# SuperUnioc_v1.net
KiCad netlist of a schematic drawn in EAGLE
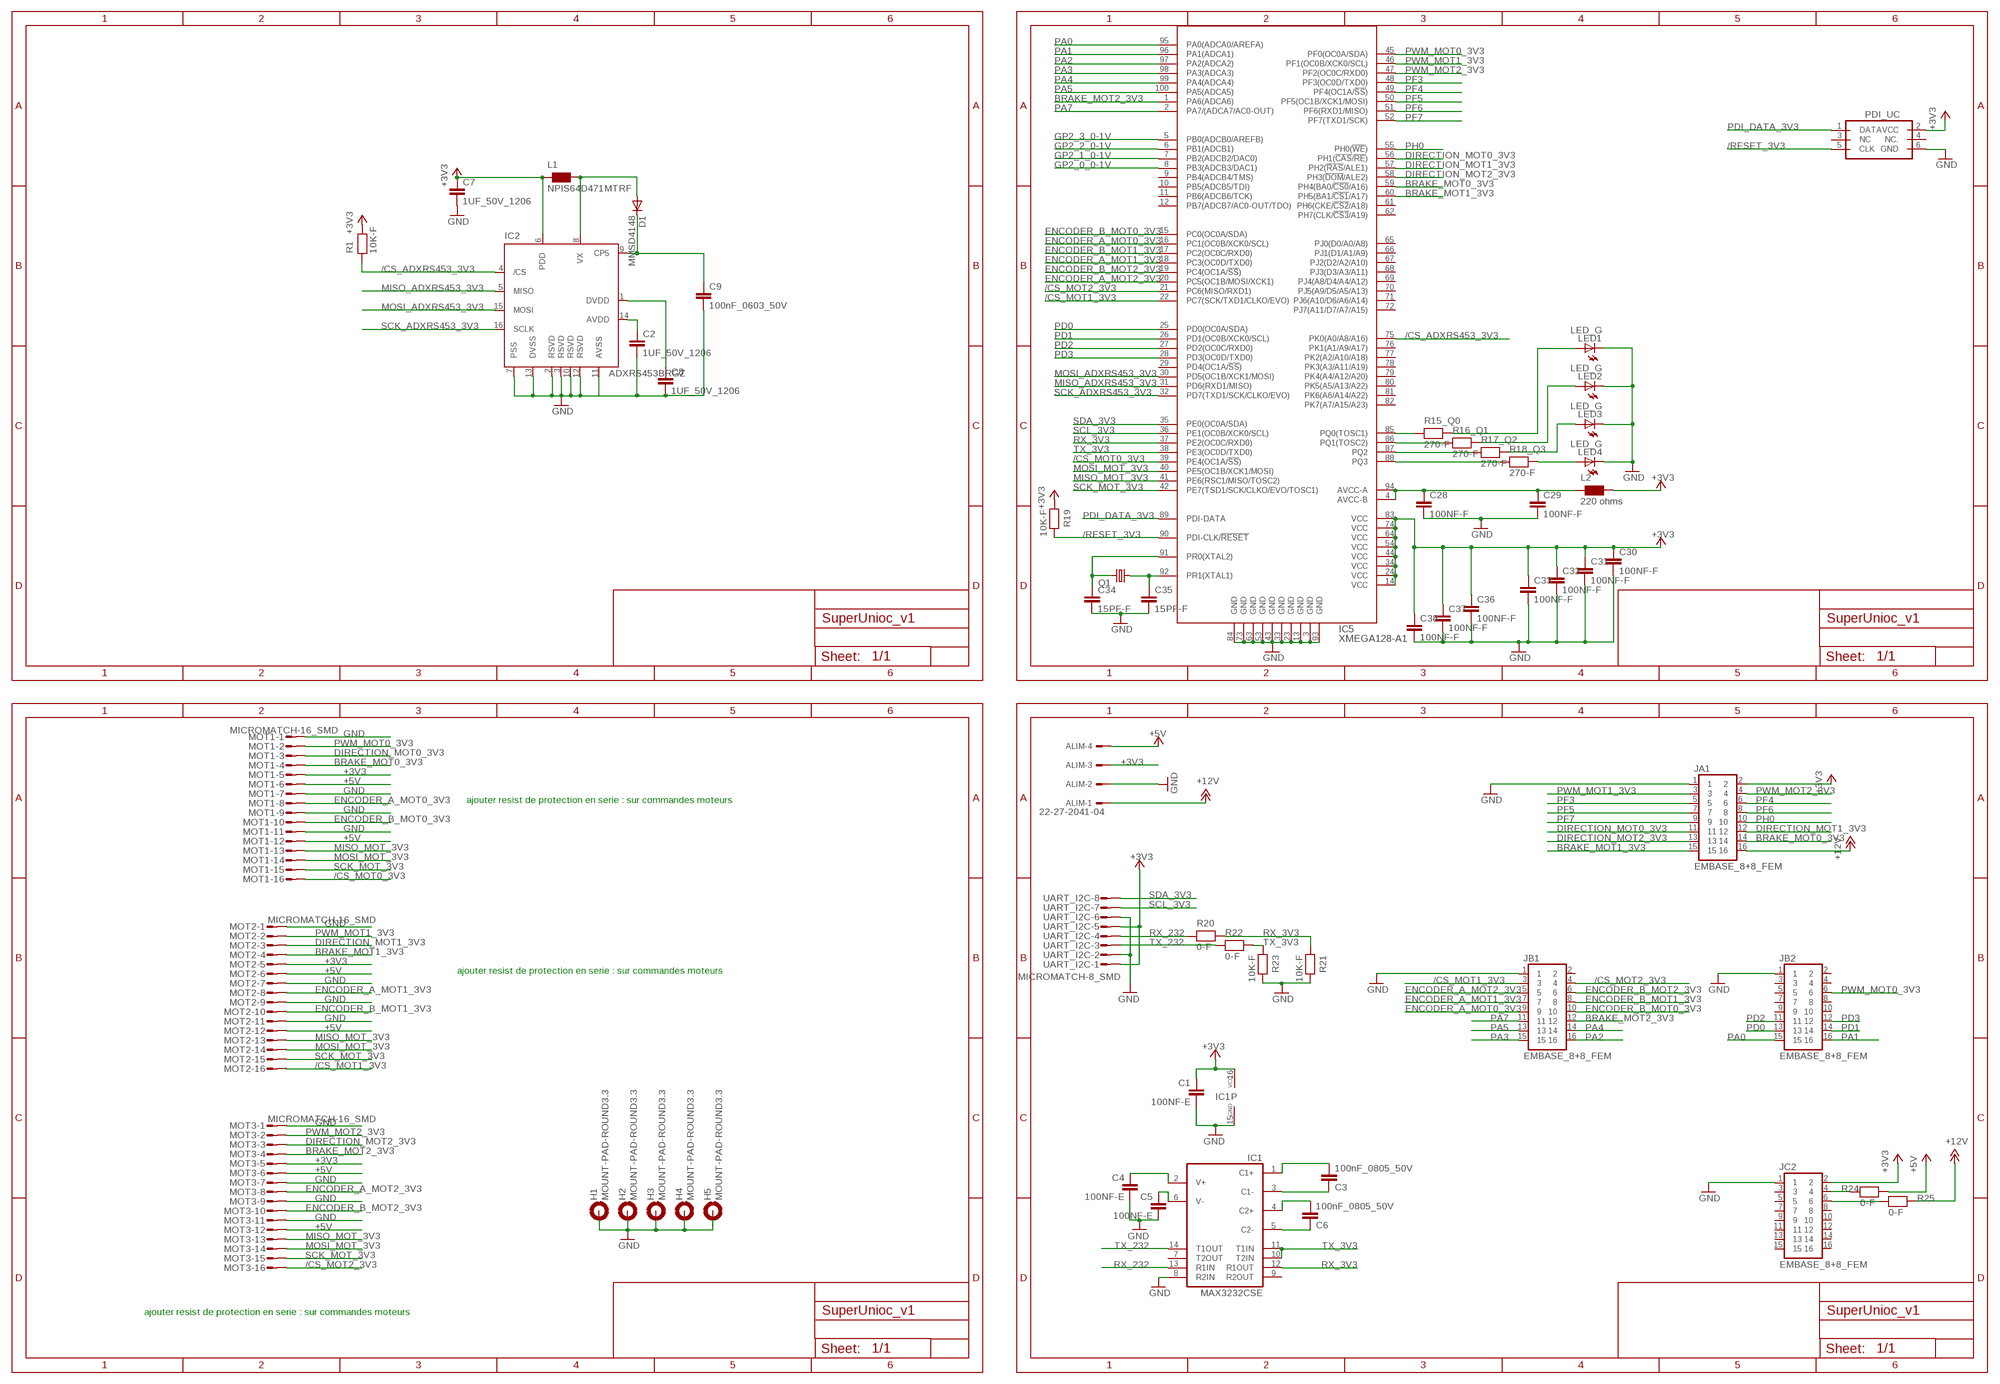
[diagram p0: schematic, sheet 1, part 1 of 2]
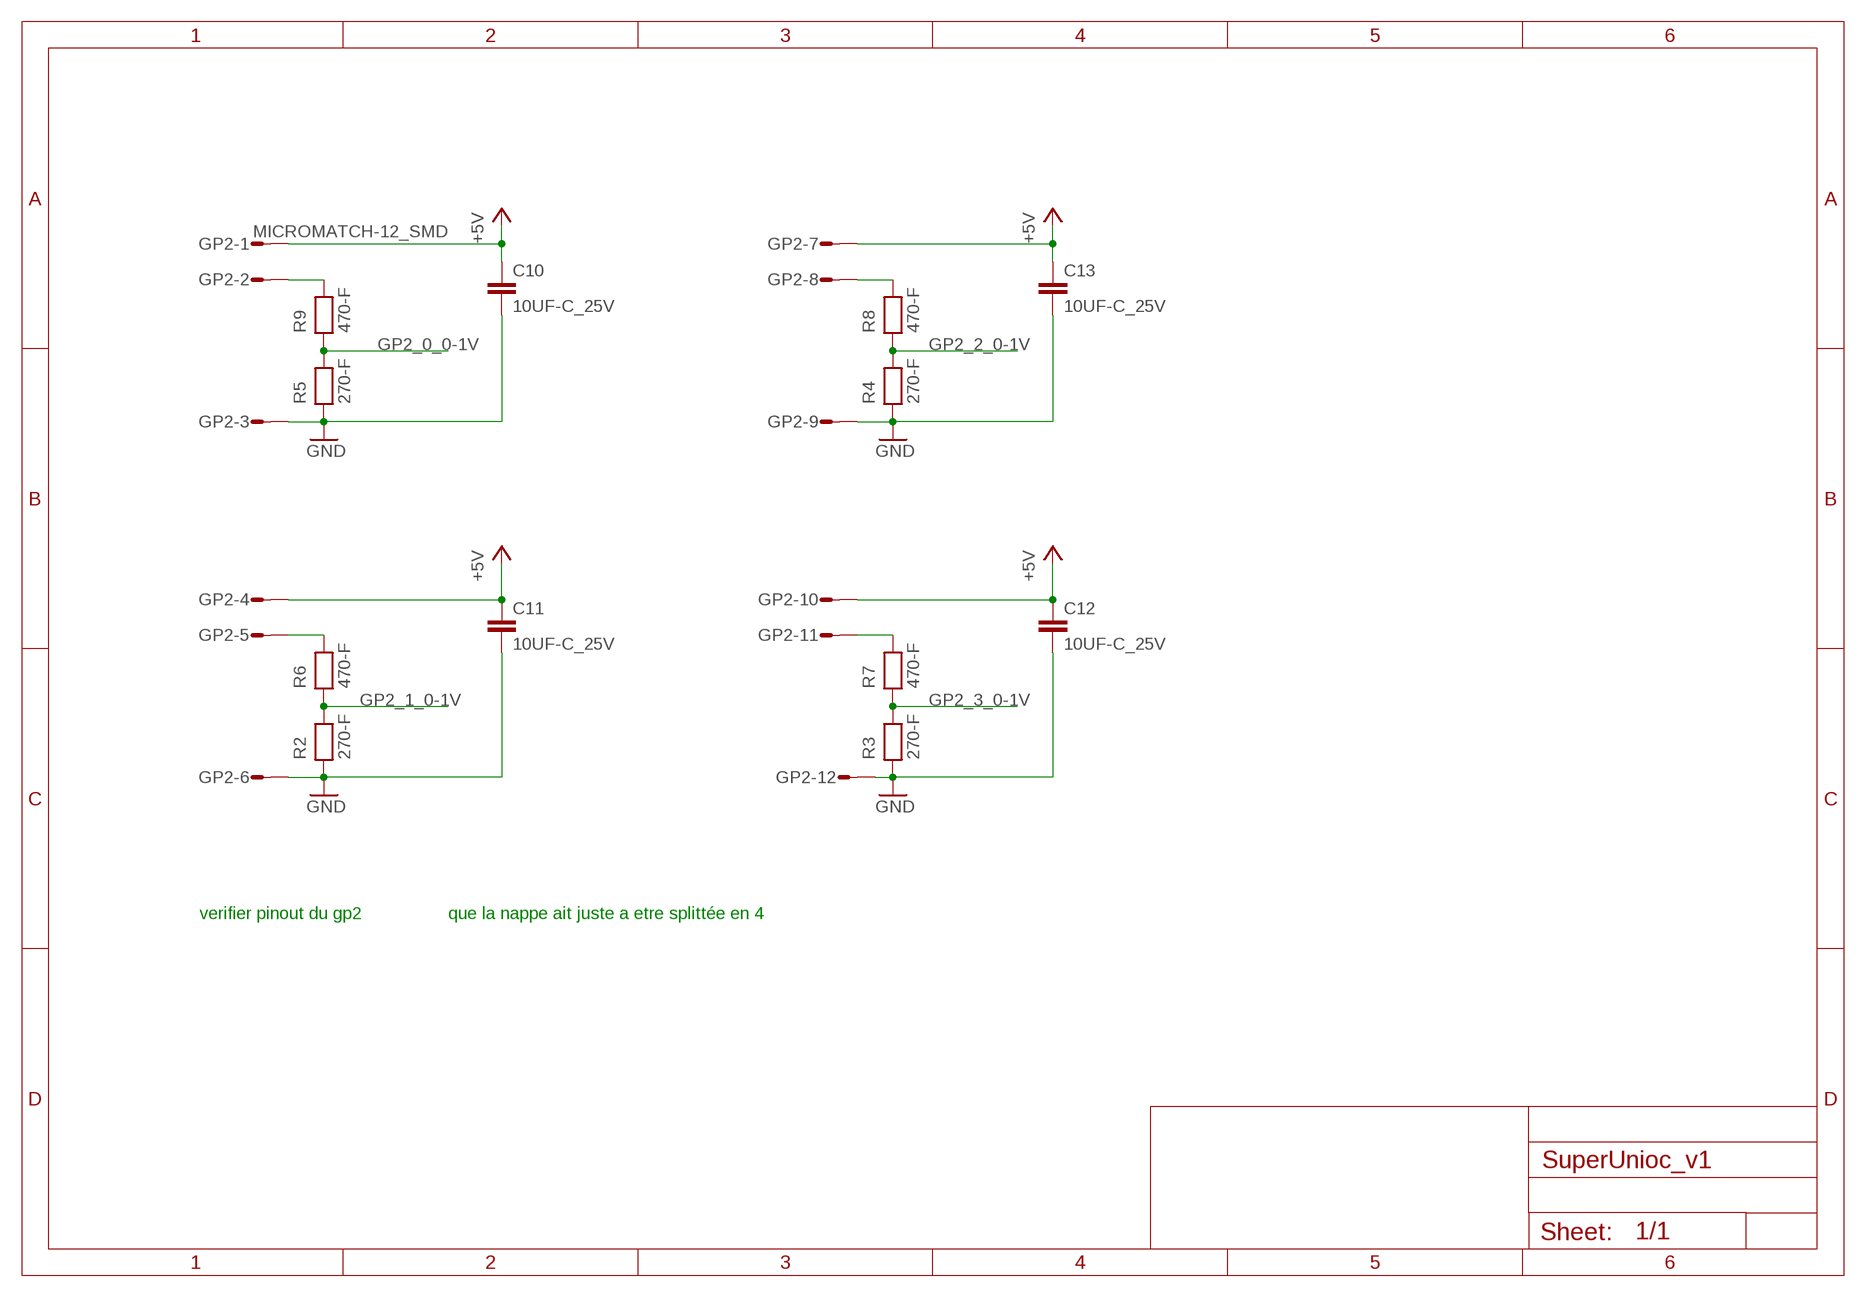
[diagram p1: schematic, sheet 1, part 2 of 2]

(export (version "E")
  (design (tool "Eeschema 10.0.6"))
  (components
    (comp (ref "ALIM")
      (value "22-27-2041-04")
      (footprint "eagle-import:6410-04")
      (libsource (lib "eagle-import") (part "22-?-0427-2041"))
    )
    (comp (ref "C1")
      (value "100NF-E")
      (footprint "eagle-import:C0805")
      (libsource (lib "eagle-import") (part "100NF-E"))
    )
    (comp (ref "C2")
      (value "1UF_50V_1206")
      (footprint "eagle-import:C1206")
      (libsource (lib "eagle-import") (part "1UFD_25V"))
    )
    (comp (ref "C3")
      (value "100nF_0805_50V")
      (footprint "eagle-import:C0805")
      (libsource (lib "eagle-import") (part "100NF-E"))
    )
    (comp (ref "C4")
      (value "100NF-E")
      (footprint "eagle-import:C0805")
      (libsource (lib "eagle-import") (part "100NF-E"))
    )
    (comp (ref "C5")
      (value "100NF-E")
      (footprint "eagle-import:C0805")
      (libsource (lib "eagle-import") (part "100NF-E"))
    )
    (comp (ref "C6")
      (value "100nF_0805_50V")
      (footprint "eagle-import:C0805")
      (libsource (lib "eagle-import") (part "100NF-E"))
    )
    (comp (ref "C7")
      (value "1UF_50V_1206")
      (footprint "eagle-import:C1206")
      (libsource (lib "eagle-import") (part "1UFD_25V"))
    )
    (comp (ref "C8")
      (value "1UF_50V_1206")
      (footprint "eagle-import:C1206")
      (libsource (lib "eagle-import") (part "1UFD_25V"))
    )
    (comp (ref "C9")
      (value "100nF_0603_50V")
      (footprint "eagle-import:C0603")
      (libsource (lib "eagle-import") (part "100NF-F"))
    )
    (comp (ref "C10")
      (value "10UF-C_25V")
      (footprint "eagle-import:C1210")
      (libsource (lib "eagle-import") (part "10UF-C_25V"))
    )
    (comp (ref "C11")
      (value "10UF-C_25V")
      (footprint "eagle-import:C1210")
      (libsource (lib "eagle-import") (part "10UF-C_25V"))
    )
    (comp (ref "C12")
      (value "10UF-C_25V")
      (footprint "eagle-import:C1210")
      (libsource (lib "eagle-import") (part "10UF-C_25V"))
    )
    (comp (ref "C13")
      (value "10UF-C_25V")
      (footprint "eagle-import:C1210")
      (libsource (lib "eagle-import") (part "10UF-C_25V"))
    )
    (comp (ref "C28")
      (value "100NF-F")
      (footprint "eagle-import:C0603")
      (libsource (lib "eagle-import") (part "100NF-F"))
    )
    (comp (ref "C29")
      (value "100NF-F")
      (footprint "eagle-import:C0603")
      (libsource (lib "eagle-import") (part "100NF-F"))
    )
    (comp (ref "C30")
      (value "100NF-F")
      (footprint "eagle-import:C0603")
      (libsource (lib "eagle-import") (part "100NF-F"))
    )
    (comp (ref "C31")
      (value "100NF-F")
      (footprint "eagle-import:C0603")
      (libsource (lib "eagle-import") (part "100NF-F"))
    )
    (comp (ref "C32")
      (value "100NF-F")
      (footprint "eagle-import:C0603")
      (libsource (lib "eagle-import") (part "100NF-F"))
    )
    (comp (ref "C33")
      (value "100NF-F")
      (footprint "eagle-import:C0603")
      (libsource (lib "eagle-import") (part "100NF-F"))
    )
    (comp (ref "C34")
      (value "15PF-F")
      (footprint "eagle-import:C0603")
      (libsource (lib "eagle-import") (part "15PF-F"))
    )
    (comp (ref "C35")
      (value "15PF-F")
      (footprint "eagle-import:C0603")
      (libsource (lib "eagle-import") (part "15PF-F"))
    )
    (comp (ref "C36")
      (value "100NF-F")
      (footprint "eagle-import:C0603")
      (libsource (lib "eagle-import") (part "100NF-F"))
    )
    (comp (ref "C37")
      (value "100NF-F")
      (footprint "eagle-import:C0603")
      (libsource (lib "eagle-import") (part "100NF-F"))
    )
    (comp (ref "C38")
      (value "100NF-F")
      (footprint "eagle-import:C0603")
      (libsource (lib "eagle-import") (part "100NF-F"))
    )
    (comp (ref "D1")
      (value "MMSD4148")
      (footprint "eagle-import:SOD123")
      (libsource (lib "eagle-import") (part "MMSD4148'"))
    )
    (comp (ref "GP2")
      (value "MICROMATCH-12_SMD")
      (footprint "eagle-import:MICROMATCH-12_SMD")
      (libsource (lib "eagle-import") (part "MICROMATCH-12_SMD"))
    )
    (comp (ref "H1")
      (value "MOUNT-PAD-ROUND3.3")
      (footprint "eagle-import:3,3-PAD")
      (libsource (lib "eagle-import") (part "MOUNT-PAD-ROUND3.3"))
    )
    (comp (ref "H2")
      (value "MOUNT-PAD-ROUND3.3")
      (footprint "eagle-import:3,3-PAD")
      (libsource (lib "eagle-import") (part "MOUNT-PAD-ROUND3.3"))
    )
    (comp (ref "H3")
      (value "MOUNT-PAD-ROUND3.3")
      (footprint "eagle-import:3,3-PAD")
      (libsource (lib "eagle-import") (part "MOUNT-PAD-ROUND3.3"))
    )
    (comp (ref "H4")
      (value "MOUNT-PAD-ROUND3.3")
      (footprint "eagle-import:3,3-PAD")
      (libsource (lib "eagle-import") (part "MOUNT-PAD-ROUND3.3"))
    )
    (comp (ref "H5")
      (value "MOUNT-PAD-ROUND3.3")
      (footprint "eagle-import:3,3-PAD")
      (libsource (lib "eagle-import") (part "MOUNT-PAD-ROUND3.3"))
    )
    (comp (ref "IC1")
      (value "MAX3232CSE")
      (footprint "eagle-import:SO16")
      (libsource (lib "eagle-import") (part "MAX3232SEC"))
    )
    (comp (ref "IC2")
      (value "ADXRS453BRGZ")
      (footprint "eagle-import:SO16_CAV")
      (libsource (lib "eagle-import") (part "ADXRS453BRG"))
    )
    (comp (ref "IC5")
      (value "XMEGA128-A1")
      (footprint "eagle-import:TQFP100")
      (libsource (lib "eagle-import") (part "XMEGA-A1TQFP"))
    )
    (comp (ref "JA1")
      (value "EMBASE_8+8_FEM")
      (footprint "eagle-import:EMBASE_8+8_FEM")
      (libsource (lib "eagle-import") (part "EMBASE_8+8_FEM"))
    )
    (comp (ref "JB1")
      (value "EMBASE_8+8_FEM")
      (footprint "eagle-import:EMBASE_8+8_FEM")
      (libsource (lib "eagle-import") (part "EMBASE_8+8_FEM"))
    )
    (comp (ref "JB2")
      (value "EMBASE_8+8_FEM")
      (footprint "eagle-import:EMBASE_8+8_FEM")
      (libsource (lib "eagle-import") (part "EMBASE_8+8_FEM"))
    )
    (comp (ref "JC2")
      (value "EMBASE_8+8_FEM")
      (footprint "eagle-import:EMBASE_8+8_FEM")
      (libsource (lib "eagle-import") (part "EMBASE_8+8_FEM"))
    )
    (comp (ref "L1")
      (value "NPIS64D471MTRF")
      (footprint "eagle-import:NPSIS_D64")
      (libsource (lib "eagle-import") (part "NPIS64D471MTRF"))
    )
    (comp (ref "L2")
      (value "220 ohms")
      (footprint "eagle-import:R0603")
      (libsource (lib "eagle-import") (part "FERRITE_220OHMS"))
    )
    (comp (ref "LED1")
      (value "LED_G")
      (footprint "eagle-import:CHIP-LED0805")
      (libsource (lib "eagle-import") (part "LED_G"))
    )
    (comp (ref "LED2")
      (value "LED_G")
      (footprint "eagle-import:CHIP-LED0805")
      (libsource (lib "eagle-import") (part "LED_G"))
    )
    (comp (ref "LED3")
      (value "LED_G")
      (footprint "eagle-import:CHIP-LED0805")
      (libsource (lib "eagle-import") (part "LED_G"))
    )
    (comp (ref "LED4")
      (value "LED_G")
      (footprint "eagle-import:CHIP-LED0805")
      (libsource (lib "eagle-import") (part "LED_G"))
    )
    (comp (ref "MOT1")
      (value "MICROMATCH-16_SMD")
      (footprint "eagle-import:MICROMATCH-16_SMD")
      (libsource (lib "eagle-import") (part "MICROMATCH-16_SMD"))
    )
    (comp (ref "MOT2")
      (value "MICROMATCH-16_SMD")
      (footprint "eagle-import:MICROMATCH-16_SMD")
      (libsource (lib "eagle-import") (part "MICROMATCH-16_SMD"))
    )
    (comp (ref "MOT3")
      (value "MICROMATCH-16_SMD")
      (footprint "eagle-import:MICROMATCH-16_SMD")
      (libsource (lib "eagle-import") (part "MICROMATCH-16_SMD"))
    )
    (comp (ref "PDI_UC")
      (value "PDI_ATMELL")
      (footprint "eagle-import:ML6L")
      (libsource (lib "eagle-import") (part "PDI_ATMELL"))
    )
    (comp (ref "Q1")
      (value "CRYSTAL_16MHZ_HC49UP")
      (footprint "eagle-import:HC49UP")
      (libsource (lib "eagle-import") (part "CRYSTAL_16MHZ_HC49UP"))
    )
    (comp (ref "R1")
      (value "10K-F")
      (footprint "eagle-import:R0603")
      (libsource (lib "eagle-import") (part "10K-F"))
    )
    (comp (ref "R2")
      (value "270-F")
      (footprint "eagle-import:R0603")
      (libsource (lib "eagle-import") (part "270-F"))
    )
    (comp (ref "R3")
      (value "270-F")
      (footprint "eagle-import:R0603")
      (libsource (lib "eagle-import") (part "270-F"))
    )
    (comp (ref "R4")
      (value "270-F")
      (footprint "eagle-import:R0603")
      (libsource (lib "eagle-import") (part "270-F"))
    )
    (comp (ref "R5")
      (value "270-F")
      (footprint "eagle-import:R0603")
      (libsource (lib "eagle-import") (part "270-F"))
    )
    (comp (ref "R6")
      (value "470-F")
      (footprint "eagle-import:R0603")
      (libsource (lib "eagle-import") (part "470-F"))
    )
    (comp (ref "R7")
      (value "470-F")
      (footprint "eagle-import:R0603")
      (libsource (lib "eagle-import") (part "470-F"))
    )
    (comp (ref "R8")
      (value "470-F")
      (footprint "eagle-import:R0603")
      (libsource (lib "eagle-import") (part "470-F"))
    )
    (comp (ref "R9")
      (value "470-F")
      (footprint "eagle-import:R0603")
      (libsource (lib "eagle-import") (part "470-F"))
    )
    (comp (ref "R15_Q0")
      (value "270-F")
      (footprint "eagle-import:R0603")
      (libsource (lib "eagle-import") (part "270-F"))
    )
    (comp (ref "R16_Q1")
      (value "270-F")
      (footprint "eagle-import:R0603")
      (libsource (lib "eagle-import") (part "270-F"))
    )
    (comp (ref "R17_Q2")
      (value "270-F")
      (footprint "eagle-import:R0603")
      (libsource (lib "eagle-import") (part "270-F"))
    )
    (comp (ref "R18_Q3")
      (value "270-F")
      (footprint "eagle-import:R0603")
      (libsource (lib "eagle-import") (part "270-F"))
    )
    (comp (ref "R19")
      (value "10K-F")
      (footprint "eagle-import:R0603")
      (libsource (lib "eagle-import") (part "10K-F"))
    )
    (comp (ref "R20")
      (value "0-F")
      (footprint "eagle-import:R0603")
      (libsource (lib "eagle-import") (part "0-F"))
    )
    (comp (ref "R21")
      (value "10K-F")
      (footprint "eagle-import:R0603")
      (libsource (lib "eagle-import") (part "10K-F"))
    )
    (comp (ref "R22")
      (value "0-F")
      (footprint "eagle-import:R0603")
      (libsource (lib "eagle-import") (part "0-F"))
    )
    (comp (ref "R23")
      (value "10K-F")
      (footprint "eagle-import:R0603")
      (libsource (lib "eagle-import") (part "10K-F"))
    )
    (comp (ref "R24")
      (value "0-F")
      (footprint "eagle-import:R0603")
      (libsource (lib "eagle-import") (part "0-F"))
    )
    (comp (ref "R25")
      (value "0-F")
      (footprint "eagle-import:R0603")
      (libsource (lib "eagle-import") (part "0-F"))
    )
    (comp (ref "UART_I2C")
      (value "MICROMATCH-8_SMD")
      (footprint "eagle-import:MICROMATCH-8_SMD")
      (libsource (lib "eagle-import") (part "MICROMATCH-8_SMD"))
    )
  )
  (nets
    (net (code "1") (name "+3V3") (class "Default")
      (node (ref "ALIM") (pin "3") (pinfunction "S_3") (pintype "passive"))
      (node (ref "C1") (pin "1") (pinfunction "1_1") (pintype "passive"))
      (node (ref "C30") (pin "1") (pinfunction "1_1") (pintype "passive"))
      (node (ref "C31") (pin "1") (pinfunction "1_1") (pintype "passive"))
      (node (ref "C32") (pin "1") (pinfunction "1_1") (pintype "passive"))
      (node (ref "C33") (pin "1") (pinfunction "1_1") (pintype "passive"))
      (node (ref "C36") (pin "1") (pinfunction "1_1") (pintype "passive"))
      (node (ref "C37") (pin "1") (pinfunction "1_1") (pintype "passive"))
      (node (ref "C38") (pin "1") (pinfunction "1_1") (pintype "passive"))
      (node (ref "C7") (pin "1") (pinfunction "1_1") (pintype "passive"))
      (node (ref "IC1") (pin "16") (pinfunction "VCC_16") (pintype "power_in"))
      (node (ref "IC2") (pin "6") (pinfunction "PDD_6") (pintype "bidirectional"))
      (node (ref "IC5") (pin "14") (pinfunction "VCC_14") (pintype "power_in"))
      (node (ref "IC5") (pin "24") (pinfunction "VCC_24") (pintype "power_in"))
      (node (ref "IC5") (pin "34") (pinfunction "VCC_34") (pintype "power_in"))
      (node (ref "IC5") (pin "44") (pinfunction "VCC_44") (pintype "power_in"))
      (node (ref "IC5") (pin "54") (pinfunction "VCC_54") (pintype "power_in"))
      (node (ref "IC5") (pin "64") (pinfunction "VCC_64") (pintype "power_in"))
      (node (ref "IC5") (pin "74") (pinfunction "VCC_74") (pintype "power_in"))
      (node (ref "IC5") (pin "83") (pinfunction "VCC_83") (pintype "power_in"))
      (node (ref "JA1") (pin "2") (pinfunction "2_2") (pintype "passive"))
      (node (ref "JC2") (pin "2") (pinfunction "2_2") (pintype "passive"))
      (node (ref "L1") (pin "1") (pinfunction "1_1") (pintype "passive"))
      (node (ref "L2") (pin "2") (pinfunction "2_2") (pintype "passive"))
      (node (ref "MOT1") (pin "5") (pinfunction "S_5") (pintype "passive"))
      (node (ref "MOT2") (pin "5") (pinfunction "S_5") (pintype "passive"))
      (node (ref "MOT3") (pin "5") (pinfunction "S_5") (pintype "passive"))
      (node (ref "PDI_UC") (pin "2") (pinfunction "VCC_2") (pintype "passive"))
      (node (ref "R1") (pin "2") (pinfunction "2_2") (pintype "bidirectional"))
      (node (ref "R19") (pin "1") (pinfunction "1_1") (pintype "bidirectional"))
      (node (ref "UART_I2C") (pin "1") (pinfunction "S_1") (pintype "passive"))
      (node (ref "UART_I2C") (pin "5") (pinfunction "S_5") (pintype "passive"))
    )
    (net (code "2") (name "+5V") (class "Default")
      (node (ref "ALIM") (pin "4") (pinfunction "S_4") (pintype "passive"))
      (node (ref "C10") (pin "1") (pinfunction "1_1") (pintype "passive"))
      (node (ref "C11") (pin "1") (pinfunction "1_1") (pintype "passive"))
      (node (ref "C12") (pin "1") (pinfunction "1_1") (pintype "passive"))
      (node (ref "C13") (pin "1") (pinfunction "1_1") (pintype "passive"))
      (node (ref "GP2") (pin "1") (pinfunction "S_1") (pintype "passive"))
      (node (ref "GP2") (pin "10") (pinfunction "S_10") (pintype "passive"))
      (node (ref "GP2") (pin "4") (pinfunction "S_4") (pintype "passive"))
      (node (ref "GP2") (pin "7") (pinfunction "S_7") (pintype "passive"))
      (node (ref "MOT1") (pin "12") (pinfunction "S_12") (pintype "passive"))
      (node (ref "MOT1") (pin "6") (pinfunction "S_6") (pintype "passive"))
      (node (ref "MOT2") (pin "12") (pinfunction "S_12") (pintype "passive"))
      (node (ref "MOT2") (pin "6") (pinfunction "S_6") (pintype "passive"))
      (node (ref "MOT3") (pin "12") (pinfunction "S_12") (pintype "passive"))
      (node (ref "MOT3") (pin "6") (pinfunction "S_6") (pintype "passive"))
      (node (ref "R24") (pin "2") (pinfunction "2_2") (pintype "bidirectional"))
    )
    (net (code "3") (name "+12V") (class "Default")
      (node (ref "ALIM") (pin "1") (pinfunction "S_1") (pintype "passive"))
      (node (ref "JA1") (pin "16") (pinfunction "16_16") (pintype "passive"))
      (node (ref "R25") (pin "2") (pinfunction "2_2") (pintype "bidirectional"))
    )
    (net (code "4") (name "/BRAKE_MOT0_3V3") (class "Default")
      (node (ref "IC5") (pin "59") (pinfunction "PH4(BA0/~{CS0}/A16)_59") (pintype "bidirectional"))
      (node (ref "JA1") (pin "14") (pinfunction "14_14") (pintype "passive"))
      (node (ref "MOT1") (pin "4") (pinfunction "S_4") (pintype "passive"))
    )
    (net (code "5") (name "/BRAKE_MOT1_3V3") (class "Default")
      (node (ref "IC5") (pin "60") (pinfunction "PH5(BA1/~{CS1}/A17)_60") (pintype "bidirectional"))
      (node (ref "JA1") (pin "15") (pinfunction "15_15") (pintype "passive"))
      (node (ref "MOT2") (pin "4") (pinfunction "S_4") (pintype "passive"))
    )
    (net (code "6") (name "/BRAKE_MOT2_3V3") (class "Default")
      (node (ref "IC5") (pin "1") (pinfunction "PA6(ADCA6)_1") (pintype "bidirectional"))
      (node (ref "JB1") (pin "12") (pinfunction "12_12") (pintype "passive"))
      (node (ref "MOT3") (pin "4") (pinfunction "S_4") (pintype "passive"))
    )
    (net (code "7") (name "/DIRECTION_MOT0_3V3") (class "Default")
      (node (ref "IC5") (pin "56") (pinfunction "PH1(~{CAS}/~{RE})_56") (pintype "bidirectional"))
      (node (ref "JA1") (pin "11") (pinfunction "11_11") (pintype "passive"))
      (node (ref "MOT1") (pin "3") (pinfunction "S_3") (pintype "passive"))
    )
    (net (code "8") (name "/DIRECTION_MOT1_3V3") (class "Default")
      (node (ref "IC5") (pin "57") (pinfunction "PH2(~{RAS}/ALE1)_57") (pintype "bidirectional"))
      (node (ref "JA1") (pin "12") (pinfunction "12_12") (pintype "passive"))
      (node (ref "MOT2") (pin "3") (pinfunction "S_3") (pintype "passive"))
    )
    (net (code "9") (name "/DIRECTION_MOT2_3V3") (class "Default")
      (node (ref "IC5") (pin "58") (pinfunction "PH3(~{DOM}/ALE2)_58") (pintype "bidirectional"))
      (node (ref "JA1") (pin "13") (pinfunction "13_13") (pintype "passive"))
      (node (ref "MOT3") (pin "3") (pinfunction "S_3") (pintype "passive"))
    )
    (net (code "10") (name "/ENCODER_A_MOT0_3V3") (class "Default")
      (node (ref "IC5") (pin "16") (pinfunction "PC1(OC0B/XCK0/SCL)_16") (pintype "bidirectional"))
      (node (ref "JB1") (pin "9") (pinfunction "9_9") (pintype "passive"))
      (node (ref "MOT1") (pin "8") (pinfunction "S_8") (pintype "passive"))
    )
    (net (code "11") (name "/ENCODER_A_MOT1_3V3") (class "Default")
      (node (ref "IC5") (pin "18") (pinfunction "PC3(OC0D/TXD0)_18") (pintype "bidirectional"))
      (node (ref "JB1") (pin "7") (pinfunction "7_7") (pintype "passive"))
      (node (ref "MOT2") (pin "8") (pinfunction "S_8") (pintype "passive"))
    )
    (net (code "12") (name "/ENCODER_A_MOT2_3V3") (class "Default")
      (node (ref "IC5") (pin "20") (pinfunction "PC5(OC1B/MOSI/XCK1)_20") (pintype "bidirectional"))
      (node (ref "JB1") (pin "5") (pinfunction "5_5") (pintype "passive"))
      (node (ref "MOT3") (pin "8") (pinfunction "S_8") (pintype "passive"))
    )
    (net (code "13") (name "/ENCODER_B_MOT0_3V3") (class "Default")
      (node (ref "IC5") (pin "15") (pinfunction "PC0(OC0A/SDA)_15") (pintype "bidirectional"))
      (node (ref "JB1") (pin "10") (pinfunction "10_10") (pintype "passive"))
      (node (ref "MOT1") (pin "10") (pinfunction "S_10") (pintype "passive"))
    )
    (net (code "14") (name "/ENCODER_B_MOT1_3V3") (class "Default")
      (node (ref "IC5") (pin "17") (pinfunction "PC2(OC0C/RXD0)_17") (pintype "bidirectional"))
      (node (ref "JB1") (pin "8") (pinfunction "8_8") (pintype "passive"))
      (node (ref "MOT2") (pin "10") (pinfunction "S_10") (pintype "passive"))
    )
    (net (code "15") (name "/ENCODER_B_MOT2_3V3") (class "Default")
      (node (ref "IC5") (pin "19") (pinfunction "PC4(OC1A/~{SS})_19") (pintype "bidirectional"))
      (node (ref "JB1") (pin "6") (pinfunction "6_6") (pintype "passive"))
      (node (ref "MOT3") (pin "10") (pinfunction "S_10") (pintype "passive"))
    )
    (net (code "16") (name "/GP2_0_0-1V") (class "Default")
      (node (ref "IC5") (pin "8") (pinfunction "PB3(ADCB3/DAC1)_8") (pintype "bidirectional"))
      (node (ref "R5") (pin "2") (pinfunction "2_2") (pintype "bidirectional"))
      (node (ref "R9") (pin "1") (pinfunction "1_1") (pintype "bidirectional"))
    )
    (net (code "17") (name "/GP2_1_0-1V") (class "Default")
      (node (ref "IC5") (pin "7") (pinfunction "PB2(ADCB2/DAC0)_7") (pintype "bidirectional"))
      (node (ref "R2") (pin "2") (pinfunction "2_2") (pintype "bidirectional"))
      (node (ref "R6") (pin "1") (pinfunction "1_1") (pintype "bidirectional"))
    )
    (net (code "18") (name "/GP2_2_0-1V") (class "Default")
      (node (ref "IC5") (pin "6") (pinfunction "PB1(ADCB1)_6") (pintype "bidirectional"))
      (node (ref "R4") (pin "2") (pinfunction "2_2") (pintype "bidirectional"))
      (node (ref "R8") (pin "1") (pinfunction "1_1") (pintype "bidirectional"))
    )
    (net (code "19") (name "/GP2_3_0-1V") (class "Default")
      (node (ref "IC5") (pin "5") (pinfunction "PB0(ADCB0/AREFB)_5") (pintype "bidirectional"))
      (node (ref "R3") (pin "2") (pinfunction "2_2") (pintype "bidirectional"))
      (node (ref "R7") (pin "1") (pinfunction "1_1") (pintype "bidirectional"))
    )
    (net (code "20") (name "/MISO_ADXRS453_3V3") (class "Default")
      (node (ref "IC2") (pin "5") (pinfunction "MISO_5") (pintype "bidirectional"))
      (node (ref "IC5") (pin "31") (pinfunction "PD6(RXD1/MISO)_31") (pintype "bidirectional"))
    )
    (net (code "21") (name "/MISO_MOT_3V3") (class "Default")
      (node (ref "IC5") (pin "41") (pinfunction "PE6(RSC1/MISO/TOSC2)_41") (pintype "bidirectional"))
      (node (ref "MOT1") (pin "13") (pinfunction "S_13") (pintype "passive"))
      (node (ref "MOT2") (pin "13") (pinfunction "S_13") (pintype "passive"))
      (node (ref "MOT3") (pin "13") (pinfunction "S_13") (pintype "passive"))
    )
    (net (code "22") (name "/MOSI_ADXRS453_3V3") (class "Default")
      (node (ref "IC2") (pin "15") (pinfunction "MOSI_15") (pintype "bidirectional"))
      (node (ref "IC5") (pin "30") (pinfunction "PD5(OC1B/XCK1/MOSI)_30") (pintype "bidirectional"))
    )
    (net (code "23") (name "/MOSI_MOT_3V3") (class "Default")
      (node (ref "IC5") (pin "40") (pinfunction "PE5(OC1B/XCK1/MOSI)_40") (pintype "bidirectional"))
      (node (ref "MOT1") (pin "14") (pinfunction "S_14") (pintype "passive"))
      (node (ref "MOT2") (pin "14") (pinfunction "S_14") (pintype "passive"))
      (node (ref "MOT3") (pin "14") (pinfunction "S_14") (pintype "passive"))
    )
    (net (code "24") (name "/PA0") (class "Default")
      (node (ref "IC5") (pin "95") (pinfunction "PA0(ADCA0/AREFA)_95") (pintype "bidirectional"))
      (node (ref "JB2") (pin "15") (pinfunction "15_15") (pintype "passive"))
    )
    (net (code "25") (name "/PA1") (class "Default")
      (node (ref "IC5") (pin "96") (pinfunction "PA1(ADCA1)_96") (pintype "bidirectional"))
      (node (ref "JB2") (pin "16") (pinfunction "16_16") (pintype "passive"))
    )
    (net (code "26") (name "/PA2") (class "Default")
      (node (ref "IC5") (pin "97") (pinfunction "PA2(ADCA2)_97") (pintype "bidirectional"))
      (node (ref "JB1") (pin "16") (pinfunction "16_16") (pintype "passive"))
    )
    (net (code "27") (name "/PA3") (class "Default")
      (node (ref "IC5") (pin "98") (pinfunction "PA3(ADCA3)_98") (pintype "bidirectional"))
      (node (ref "JB1") (pin "15") (pinfunction "15_15") (pintype "passive"))
    )
    (net (code "28") (name "/PA4") (class "Default")
      (node (ref "IC5") (pin "99") (pinfunction "PA4(ADCA4)_99") (pintype "bidirectional"))
      (node (ref "JB1") (pin "14") (pinfunction "14_14") (pintype "passive"))
    )
    (net (code "29") (name "/PA5") (class "Default")
      (node (ref "IC5") (pin "100") (pinfunction "PA5(ADCA5)_100") (pintype "bidirectional"))
      (node (ref "JB1") (pin "13") (pinfunction "13_13") (pintype "passive"))
    )
    (net (code "30") (name "/PA7") (class "Default")
      (node (ref "IC5") (pin "2") (pinfunction "PA7/(ADCA7/AC0-OUT)_2") (pintype "bidirectional"))
      (node (ref "JB1") (pin "11") (pinfunction "11_11") (pintype "passive"))
    )
    (net (code "31") (name "/PD0") (class "Default")
      (node (ref "IC5") (pin "25") (pinfunction "PD0(OC0A/SDA)_25") (pintype "bidirectional"))
      (node (ref "JB2") (pin "13") (pinfunction "13_13") (pintype "passive"))
    )
    (net (code "32") (name "/PD1") (class "Default")
      (node (ref "IC5") (pin "26") (pinfunction "PD1(OC0B/XCK0/SCL)_26") (pintype "bidirectional"))
      (node (ref "JB2") (pin "14") (pinfunction "14_14") (pintype "passive"))
    )
    (net (code "33") (name "/PD2") (class "Default")
      (node (ref "IC5") (pin "27") (pinfunction "PD2(OC0C/RXD0)_27") (pintype "bidirectional"))
      (node (ref "JB2") (pin "11") (pinfunction "11_11") (pintype "passive"))
    )
    (net (code "34") (name "/PD3") (class "Default")
      (node (ref "IC5") (pin "28") (pinfunction "PD3(OC0D/TXD0)_28") (pintype "bidirectional"))
      (node (ref "JB2") (pin "12") (pinfunction "12_12") (pintype "passive"))
    )
    (net (code "35") (name "/PDI_DATA_3V3") (class "Default")
      (node (ref "IC5") (pin "89") (pinfunction "PDI-DATA_89") (pintype "bidirectional"))
      (node (ref "PDI_UC") (pin "1") (pinfunction "DATA_1") (pintype "passive"))
    )
    (net (code "36") (name "/PF3") (class "Default")
      (node (ref "IC5") (pin "48") (pinfunction "PF3(OC0D/TXD0)_48") (pintype "bidirectional"))
      (node (ref "JA1") (pin "5") (pinfunction "5_5") (pintype "passive"))
    )
    (net (code "37") (name "/PF4") (class "Default")
      (node (ref "IC5") (pin "49") (pinfunction "PF4(OC1A/~{SS})_49") (pintype "bidirectional"))
      (node (ref "JA1") (pin "6") (pinfunction "6_6") (pintype "passive"))
    )
    (net (code "38") (name "/PF5") (class "Default")
      (node (ref "IC5") (pin "50") (pinfunction "PF5(OC1B/XCK1/MOSI)_50") (pintype "bidirectional"))
      (node (ref "JA1") (pin "7") (pinfunction "7_7") (pintype "passive"))
    )
    (net (code "39") (name "/PF6") (class "Default")
      (node (ref "IC5") (pin "51") (pinfunction "PF6(RXD1/MISO)_51") (pintype "bidirectional"))
      (node (ref "JA1") (pin "8") (pinfunction "8_8") (pintype "passive"))
    )
    (net (code "40") (name "/PF7") (class "Default")
      (node (ref "IC5") (pin "52") (pinfunction "PF7(TXD1/SCK)_52") (pintype "bidirectional"))
      (node (ref "JA1") (pin "9") (pinfunction "9_9") (pintype "passive"))
    )
    (net (code "41") (name "/PH0") (class "Default")
      (node (ref "IC5") (pin "55") (pinfunction "PH0(~{WE})_55") (pintype "bidirectional"))
      (node (ref "JA1") (pin "10") (pinfunction "10_10") (pintype "passive"))
    )
    (net (code "42") (name "/PWM_MOT0_3V3") (class "Default")
      (node (ref "IC5") (pin "45") (pinfunction "PF0(OC0A/SDA)_45") (pintype "bidirectional"))
      (node (ref "JB2") (pin "6") (pinfunction "6_6") (pintype "passive"))
      (node (ref "MOT1") (pin "2") (pinfunction "S_2") (pintype "passive"))
    )
    (net (code "43") (name "/PWM_MOT1_3V3") (class "Default")
      (node (ref "IC5") (pin "46") (pinfunction "PF1(OC0B/XCK0/SCL)_46") (pintype "bidirectional"))
      (node (ref "JA1") (pin "3") (pinfunction "3_3") (pintype "passive"))
      (node (ref "MOT2") (pin "2") (pinfunction "S_2") (pintype "passive"))
    )
    (net (code "44") (name "/PWM_MOT2_3V3") (class "Default")
      (node (ref "IC5") (pin "47") (pinfunction "PF2(OC0C/RXD0)_47") (pintype "bidirectional"))
      (node (ref "JA1") (pin "4") (pinfunction "4_4") (pintype "passive"))
      (node (ref "MOT3") (pin "2") (pinfunction "S_2") (pintype "passive"))
    )
    (net (code "45") (name "/RX_3V3") (class "Default")
      (node (ref "IC1") (pin "12") (pinfunction "R1OUT_12") (pintype "output"))
      (node (ref "IC5") (pin "37") (pinfunction "PE2(OC0C/RXD0)_37") (pintype "bidirectional"))
      (node (ref "R20") (pin "2") (pinfunction "2_2") (pintype "bidirectional"))
      (node (ref "R21") (pin "1") (pinfunction "1_1") (pintype "bidirectional"))
    )
    (net (code "46") (name "/RX_232") (class "Default")
      (node (ref "IC1") (pin "13") (pinfunction "R1IN_13") (pintype "input"))
      (node (ref "R20") (pin "1") (pinfunction "1_1") (pintype "bidirectional"))
      (node (ref "UART_I2C") (pin "4") (pinfunction "S_4") (pintype "passive"))
    )
    (net (code "47") (name "/SCK_ADXRS453_3V3") (class "Default")
      (node (ref "IC2") (pin "16") (pinfunction "SCLK_16") (pintype "bidirectional"))
      (node (ref "IC5") (pin "32") (pinfunction "PD7(TXD1/SCK/CLKO/EVO)_32") (pintype "bidirectional"))
    )
    (net (code "48") (name "/SCK_MOT_3V3") (class "Default")
      (node (ref "IC5") (pin "42") (pinfunction "PE7(TSD1/SCK/CLKO/EVO/TOSC1)_42") (pintype "bidirectional"))
      (node (ref "MOT1") (pin "15") (pinfunction "S_15") (pintype "passive"))
      (node (ref "MOT2") (pin "15") (pinfunction "S_15") (pintype "passive"))
      (node (ref "MOT3") (pin "15") (pinfunction "S_15") (pintype "passive"))
    )
    (net (code "49") (name "/SCL_3V3") (class "Default")
      (node (ref "IC5") (pin "36") (pinfunction "PE1(OC0B/XCK0/SCL)_36") (pintype "bidirectional"))
      (node (ref "UART_I2C") (pin "7") (pinfunction "S_7") (pintype "passive"))
    )
    (net (code "50") (name "/SDA_3V3") (class "Default")
      (node (ref "IC5") (pin "35") (pinfunction "PE0(OC0A/SDA)_35") (pintype "bidirectional"))
      (node (ref "UART_I2C") (pin "8") (pinfunction "S_8") (pintype "passive"))
    )
    (net (code "51") (name "/TX_3V3") (class "Default")
      (node (ref "IC1") (pin "10") (pinfunction "T2IN_10") (pintype "input"))
      (node (ref "IC1") (pin "11") (pinfunction "T1IN_11") (pintype "input"))
      (node (ref "IC5") (pin "38") (pinfunction "PE3(OC0D/TXD0)_38") (pintype "bidirectional"))
      (node (ref "R22") (pin "2") (pinfunction "2_2") (pintype "bidirectional"))
      (node (ref "R23") (pin "1") (pinfunction "1_1") (pintype "bidirectional"))
    )
    (net (code "52") (name "/TX_232") (class "Default")
      (node (ref "IC1") (pin "14") (pinfunction "T1OUT_14") (pintype "output"))
      (node (ref "R22") (pin "1") (pinfunction "1_1") (pintype "bidirectional"))
      (node (ref "UART_I2C") (pin "3") (pinfunction "S_3") (pintype "passive"))
    )
    (net (code "53") (name "/{slash}CS_ADXRS453_3V3") (class "Default")
      (node (ref "IC2") (pin "4") (pinfunction "/CS_4") (pintype "bidirectional"))
      (node (ref "IC5") (pin "75") (pinfunction "PK0(A0/A8/A16)_75") (pintype "bidirectional"))
      (node (ref "R1") (pin "1") (pinfunction "1_1") (pintype "bidirectional"))
    )
    (net (code "54") (name "/{slash}CS_MOT0_3V3") (class "Default")
      (node (ref "IC5") (pin "39") (pinfunction "PE4(OC1A/~{SS})_39") (pintype "bidirectional"))
      (node (ref "MOT1") (pin "16") (pinfunction "S_16") (pintype "passive"))
    )
    (net (code "55") (name "/{slash}CS_MOT1_3V3") (class "Default")
      (node (ref "IC5") (pin "22") (pinfunction "PC7(SCK/TXD1/CLKO/EVO)_22") (pintype "bidirectional"))
      (node (ref "JB1") (pin "3") (pinfunction "3_3") (pintype "passive"))
      (node (ref "MOT2") (pin "16") (pinfunction "S_16") (pintype "passive"))
    )
    (net (code "56") (name "/{slash}CS_MOT2_3V3") (class "Default")
      (node (ref "IC5") (pin "21") (pinfunction "PC6(MISO/RXD1)_21") (pintype "bidirectional"))
      (node (ref "JB1") (pin "4") (pinfunction "4_4") (pintype "passive"))
      (node (ref "MOT3") (pin "16") (pinfunction "S_16") (pintype "passive"))
    )
    (net (code "57") (name "/{slash}RESET_3V3") (class "Default")
      (node (ref "IC5") (pin "90") (pinfunction "PDI-CLK/~{RESET}_90") (pintype "input"))
      (node (ref "PDI_UC") (pin "5") (pinfunction "CLK_5") (pintype "passive"))
      (node (ref "R19") (pin "2") (pinfunction "2_2") (pintype "bidirectional"))
    )
    (net (code "58") (name "GND") (class "Default")
      (node (ref "ALIM") (pin "2") (pinfunction "S_2") (pintype "passive"))
      (node (ref "C1") (pin "2") (pinfunction "2_2") (pintype "passive"))
      (node (ref "C10") (pin "2") (pinfunction "2_2") (pintype "passive"))
      (node (ref "C11") (pin "2") (pinfunction "2_2") (pintype "passive"))
      (node (ref "C12") (pin "2") (pinfunction "2_2") (pintype "passive"))
      (node (ref "C13") (pin "2") (pinfunction "2_2") (pintype "passive"))
      (node (ref "C2") (pin "2") (pinfunction "2_2") (pintype "passive"))
      (node (ref "C28") (pin "2") (pinfunction "2_2") (pintype "passive"))
      (node (ref "C29") (pin "2") (pinfunction "2_2") (pintype "passive"))
      (node (ref "C30") (pin "2") (pinfunction "2_2") (pintype "passive"))
      (node (ref "C31") (pin "2") (pinfunction "2_2") (pintype "passive"))
      (node (ref "C32") (pin "2") (pinfunction "2_2") (pintype "passive"))
      (node (ref "C33") (pin "2") (pinfunction "2_2") (pintype "passive"))
      (node (ref "C34") (pin "2") (pinfunction "2_2") (pintype "passive"))
      (node (ref "C35") (pin "2") (pinfunction "2_2") (pintype "passive"))
      (node (ref "C36") (pin "2") (pinfunction "2_2") (pintype "passive"))
      (node (ref "C37") (pin "2") (pinfunction "2_2") (pintype "passive"))
      (node (ref "C38") (pin "2") (pinfunction "2_2") (pintype "passive"))
      (node (ref "C4") (pin "2") (pinfunction "2_2") (pintype "passive"))
      (node (ref "C5") (pin "2") (pinfunction "2_2") (pintype "passive"))
      (node (ref "C7") (pin "2") (pinfunction "2_2") (pintype "passive"))
      (node (ref "C8") (pin "2") (pinfunction "2_2") (pintype "passive"))
      (node (ref "C9") (pin "2") (pinfunction "2_2") (pintype "passive"))
      (node (ref "GP2") (pin "12") (pinfunction "S_12") (pintype "passive"))
      (node (ref "GP2") (pin "3") (pinfunction "S_3") (pintype "passive"))
      (node (ref "GP2") (pin "6") (pinfunction "S_6") (pintype "passive"))
      (node (ref "GP2") (pin "9") (pinfunction "S_9") (pintype "passive"))
      (node (ref "H1") (pin "B3,3") (pinfunction "MOUNT_B3,3") (pintype "passive"))
      (node (ref "H2") (pin "B3,3") (pinfunction "MOUNT_B3,3") (pintype "passive"))
      (node (ref "H3") (pin "B3,3") (pinfunction "MOUNT_B3,3") (pintype "passive"))
      (node (ref "H4") (pin "B3,3") (pinfunction "MOUNT_B3,3") (pintype "passive"))
      (node (ref "H5") (pin "B3,3") (pinfunction "MOUNT_B3,3") (pintype "passive"))
      (node (ref "IC1") (pin "15") (pinfunction "GND_15") (pintype "power_in"))
      (node (ref "IC1") (pin "8") (pinfunction "R2IN_8") (pintype "input"))
      (node (ref "IC2") (pin "10") (pinfunction "RSVD_10") (pintype "bidirectional"))
      (node (ref "IC2") (pin "11") (pinfunction "AVSS_11") (pintype "bidirectional"))
      (node (ref "IC2") (pin "12") (pinfunction "RSVD_12") (pintype "bidirectional"))
      (node (ref "IC2") (pin "13") (pinfunction "DVSS_13") (pintype "bidirectional"))
      (node (ref "IC2") (pin "2") (pinfunction "RSVD_2") (pintype "bidirectional"))
      (node (ref "IC2") (pin "3") (pinfunction "RSVD_3") (pintype "bidirectional"))
      (node (ref "IC2") (pin "7") (pinfunction "PSS_7") (pintype "bidirectional"))
      (node (ref "IC5") (pin "13") (pinfunction "GND_13") (pintype "power_in"))
      (node (ref "IC5") (pin "23") (pinfunction "GND_23") (pintype "power_in"))
      (node (ref "IC5") (pin "3") (pinfunction "GND_3") (pintype "power_in"))
      (node (ref "IC5") (pin "33") (pinfunction "GND_33") (pintype "power_in"))
      (node (ref "IC5") (pin "43") (pinfunction "GND_43") (pintype "power_in"))
      (node (ref "IC5") (pin "53") (pinfunction "GND_53") (pintype "power_in"))
      (node (ref "IC5") (pin "63") (pinfunction "GND_63") (pintype "power_in"))
      (node (ref "IC5") (pin "73") (pinfunction "GND_73") (pintype "power_in"))
      (node (ref "IC5") (pin "84") (pinfunction "GND_84") (pintype "power_in"))
      (node (ref "IC5") (pin "93") (pinfunction "GND_93") (pintype "power_in"))
      (node (ref "JA1") (pin "1") (pinfunction "1_1") (pintype "passive"))
      (node (ref "JB1") (pin "1") (pinfunction "1_1") (pintype "passive"))
      (node (ref "JB2") (pin "1") (pinfunction "1_1") (pintype "passive"))
      (node (ref "JC2") (pin "1") (pinfunction "1_1") (pintype "passive"))
      (node (ref "LED1") (pin "C") (pinfunction "C_C") (pintype "passive"))
      (node (ref "LED2") (pin "C") (pinfunction "C_C") (pintype "passive"))
      (node (ref "LED3") (pin "C") (pinfunction "C_C") (pintype "passive"))
      (node (ref "LED4") (pin "C") (pinfunction "C_C") (pintype "passive"))
      (node (ref "MOT1") (pin "1") (pinfunction "S_1") (pintype "passive"))
      (node (ref "MOT1") (pin "11") (pinfunction "S_11") (pintype "passive"))
      (node (ref "MOT1") (pin "7") (pinfunction "S_7") (pintype "passive"))
      (node (ref "MOT1") (pin "9") (pinfunction "S_9") (pintype "passive"))
      (node (ref "MOT2") (pin "1") (pinfunction "S_1") (pintype "passive"))
      (node (ref "MOT2") (pin "11") (pinfunction "S_11") (pintype "passive"))
      (node (ref "MOT2") (pin "7") (pinfunction "S_7") (pintype "passive"))
      (node (ref "MOT2") (pin "9") (pinfunction "S_9") (pintype "passive"))
      (node (ref "MOT3") (pin "1") (pinfunction "S_1") (pintype "passive"))
      (node (ref "MOT3") (pin "11") (pinfunction "S_11") (pintype "passive"))
      (node (ref "MOT3") (pin "7") (pinfunction "S_7") (pintype "passive"))
      (node (ref "MOT3") (pin "9") (pinfunction "S_9") (pintype "passive"))
      (node (ref "PDI_UC") (pin "6") (pinfunction "GND_6") (pintype "passive"))
      (node (ref "R2") (pin "1") (pinfunction "1_1") (pintype "bidirectional"))
      (node (ref "R21") (pin "2") (pinfunction "2_2") (pintype "bidirectional"))
      (node (ref "R23") (pin "2") (pinfunction "2_2") (pintype "bidirectional"))
      (node (ref "R3") (pin "1") (pinfunction "1_1") (pintype "bidirectional"))
      (node (ref "R4") (pin "1") (pinfunction "1_1") (pintype "bidirectional"))
      (node (ref "R5") (pin "1") (pinfunction "1_1") (pintype "bidirectional"))
      (node (ref "UART_I2C") (pin "2") (pinfunction "S_2") (pintype "passive"))
      (node (ref "UART_I2C") (pin "6") (pinfunction "S_6") (pintype "passive"))
    )
    (net (code "59") (name "Net-(GP2C-S)") (class "Default")
      (node (ref "GP2") (pin "11") (pinfunction "S_11") (pintype "passive"))
      (node (ref "R7") (pin "2") (pinfunction "2_2") (pintype "bidirectional"))
    )
    (net (code "60") (name "Net-(GP2E-S)") (class "Default")
      (node (ref "GP2") (pin "2") (pinfunction "S_2") (pintype "passive"))
      (node (ref "R9") (pin "2") (pinfunction "2_2") (pintype "bidirectional"))
    )
    (net (code "61") (name "Net-(GP2H-S)") (class "Default")
      (node (ref "GP2") (pin "5") (pinfunction "S_5") (pintype "passive"))
      (node (ref "R6") (pin "2") (pinfunction "2_2") (pintype "bidirectional"))
    )
    (net (code "62") (name "Net-(GP2K-S)") (class "Default")
      (node (ref "GP2") (pin "8") (pinfunction "S_8") (pintype "passive"))
      (node (ref "R8") (pin "2") (pinfunction "2_2") (pintype "bidirectional"))
    )
    (net (code "63") (name "Net-(IC1A-C1+)") (class "Default")
      (node (ref "C3") (pin "1") (pinfunction "1_1") (pintype "passive"))
      (node (ref "IC1") (pin "1") (pinfunction "C1+_1") (pintype "bidirectional"))
    )
    (net (code "64") (name "Net-(IC1A-C1-)") (class "Default")
      (node (ref "C3") (pin "2") (pinfunction "2_2") (pintype "passive"))
      (node (ref "IC1") (pin "3") (pinfunction "C1-_3") (pintype "bidirectional"))
    )
    (net (code "65") (name "Net-(IC1A-C2+)") (class "Default")
      (node (ref "C6") (pin "1") (pinfunction "1_1") (pintype "passive"))
      (node (ref "IC1") (pin "4") (pinfunction "C2+_4") (pintype "bidirectional"))
    )
    (net (code "66") (name "Net-(IC1A-C2-)") (class "Default")
      (node (ref "C6") (pin "2") (pinfunction "2_2") (pintype "passive"))
      (node (ref "IC1") (pin "5") (pinfunction "C2-_5") (pintype "bidirectional"))
    )
    (net (code "67") (name "Net-(IC1A-V+)") (class "Default")
      (node (ref "C4") (pin "1") (pinfunction "1_1") (pintype "passive"))
      (node (ref "IC1") (pin "2") (pinfunction "V+_2") (pintype "bidirectional"))
    )
    (net (code "68") (name "Net-(IC1A-V-)") (class "Default")
      (node (ref "C5") (pin "1") (pinfunction "1_1") (pintype "passive"))
      (node (ref "IC1") (pin "6") (pinfunction "V-_6") (pintype "bidirectional"))
    )
    (net (code "69") (name "Net-(IC2-AVDD)") (class "Default")
      (node (ref "C2") (pin "1") (pinfunction "1_1") (pintype "passive"))
      (node (ref "IC2") (pin "14") (pinfunction "AVDD_14") (pintype "bidirectional"))
    )
    (net (code "70") (name "Net-(IC2-CP5)") (class "Default")
      (node (ref "C9") (pin "1") (pinfunction "1_1") (pintype "passive"))
      (node (ref "D1") (pin "C") (pinfunction "C_C") (pintype "passive"))
      (node (ref "IC2") (pin "9") (pinfunction "CP5_9") (pintype "bidirectional"))
    )
    (net (code "71") (name "Net-(IC2-DVDD)") (class "Default")
      (node (ref "C8") (pin "1") (pinfunction "1_1") (pintype "passive"))
      (node (ref "IC2") (pin "1") (pinfunction "DVDD_1") (pintype "bidirectional"))
    )
    (net (code "72") (name "Net-(IC2-VX)") (class "Default")
      (node (ref "D1") (pin "A") (pinfunction "A_A") (pintype "passive"))
      (node (ref "IC2") (pin "8") (pinfunction "VX_8") (pintype "bidirectional"))
      (node (ref "L1") (pin "2") (pinfunction "2_2") (pintype "passive"))
    )
    (net (code "73") (name "Net-(IC5-AVCC-A)") (class "Default")
      (node (ref "C28") (pin "1") (pinfunction "1_1") (pintype "passive"))
      (node (ref "C29") (pin "1") (pinfunction "1_1") (pintype "passive"))
      (node (ref "IC5") (pin "4") (pinfunction "AVCC-B_4") (pintype "power_in"))
      (node (ref "IC5") (pin "94") (pinfunction "AVCC-A_94") (pintype "power_in"))
      (node (ref "L2") (pin "1") (pinfunction "1_1") (pintype "passive"))
    )
    (net (code "74") (name "Net-(IC5-PQ0(TOSC1))") (class "Default")
      (node (ref "IC5") (pin "85") (pinfunction "PQ0(TOSC1)_85") (pintype "bidirectional"))
      (node (ref "R15_Q0") (pin "1") (pinfunction "1_1") (pintype "bidirectional"))
    )
    (net (code "75") (name "Net-(IC5-PQ1(TOSC2))") (class "Default")
      (node (ref "IC5") (pin "86") (pinfunction "PQ1(TOSC2)_86") (pintype "bidirectional"))
      (node (ref "R16_Q1") (pin "1") (pinfunction "1_1") (pintype "bidirectional"))
    )
    (net (code "76") (name "Net-(IC5-PQ2)") (class "Default")
      (node (ref "IC5") (pin "87") (pinfunction "PQ2_87") (pintype "bidirectional"))
      (node (ref "R17_Q2") (pin "1") (pinfunction "1_1") (pintype "bidirectional"))
    )
    (net (code "77") (name "Net-(IC5-PQ3)") (class "Default")
      (node (ref "IC5") (pin "88") (pinfunction "PQ3_88") (pintype "bidirectional"))
      (node (ref "R18_Q3") (pin "1") (pinfunction "1_1") (pintype "bidirectional"))
    )
    (net (code "78") (name "Net-(IC5-PR0(XTAL2))") (class "Default")
      (node (ref "C34") (pin "1") (pinfunction "1_1") (pintype "passive"))
      (node (ref "IC5") (pin "91") (pinfunction "PR0(XTAL2)_91") (pintype "bidirectional"))
      (node (ref "Q1") (pin "2") (pinfunction "2_2") (pintype "passive"))
    )
    (net (code "79") (name "Net-(IC5-PR1(XTAL1))") (class "Default")
      (node (ref "C35") (pin "1") (pinfunction "1_1") (pintype "passive"))
      (node (ref "IC5") (pin "92") (pinfunction "PR1(XTAL1)_92") (pintype "bidirectional"))
      (node (ref "Q1") (pin "1") (pinfunction "1_1") (pintype "passive"))
    )
    (net (code "80") (name "Net-(JC2-Pad4)") (class "Default")
      (node (ref "JC2") (pin "4") (pinfunction "4_4") (pintype "passive"))
      (node (ref "R24") (pin "1") (pinfunction "1_1") (pintype "bidirectional"))
    )
    (net (code "81") (name "Net-(JC2-Pad6)") (class "Default")
      (node (ref "JC2") (pin "6") (pinfunction "6_6") (pintype "passive"))
      (node (ref "R25") (pin "1") (pinfunction "1_1") (pintype "bidirectional"))
    )
    (net (code "82") (name "Net-(LED1-PadA)") (class "Default")
      (node (ref "LED1") (pin "A") (pinfunction "A_A") (pintype "passive"))
      (node (ref "R15_Q0") (pin "2") (pinfunction "2_2") (pintype "bidirectional"))
    )
    (net (code "83") (name "Net-(LED2-PadA)") (class "Default")
      (node (ref "LED2") (pin "A") (pinfunction "A_A") (pintype "passive"))
      (node (ref "R16_Q1") (pin "2") (pinfunction "2_2") (pintype "bidirectional"))
    )
    (net (code "84") (name "Net-(LED3-PadA)") (class "Default")
      (node (ref "LED3") (pin "A") (pinfunction "A_A") (pintype "passive"))
      (node (ref "R17_Q2") (pin "2") (pinfunction "2_2") (pintype "bidirectional"))
    )
    (net (code "85") (name "Net-(LED4-PadA)") (class "Default")
      (node (ref "LED4") (pin "A") (pinfunction "A_A") (pintype "passive"))
      (node (ref "R18_Q3") (pin "2") (pinfunction "2_2") (pintype "bidirectional"))
    )
    (net (code "86") (name "unconnected-(IC1A-R2OUT-Pad9)") (class "Default")
      (node (ref "IC1") (pin "9") (pinfunction "R2OUT_9") (pintype "output"))
    )
    (net (code "87") (name "unconnected-(IC1A-T2OUT-Pad7)") (class "Default")
      (node (ref "IC1") (pin "7") (pinfunction "T2OUT_7") (pintype "output"))
    )
    (net (code "88") (name "unconnected-(IC5-PB4(ADCB4{slash}TMS)-Pad9)") (class "Default")
      (node (ref "IC5") (pin "9") (pinfunction "PB4(ADCB4/TMS)_9") (pintype "bidirectional"))
    )
    (net (code "89") (name "unconnected-(IC5-PB5(ADCB5{slash}TDI)-Pad10)") (class "Default")
      (node (ref "IC5") (pin "10") (pinfunction "PB5(ADCB5/TDI)_10") (pintype "bidirectional"))
    )
    (net (code "90") (name "unconnected-(IC5-PB6(ADCB6{slash}TCK)-Pad11)") (class "Default")
      (node (ref "IC5") (pin "11") (pinfunction "PB6(ADCB6/TCK)_11") (pintype "bidirectional"))
    )
    (net (code "91") (name "unconnected-(IC5-PB7(ADCB7{slash}AC0-OUT{slash}TDO)-Pad12)") (class "Default")
      (node (ref "IC5") (pin "12") (pinfunction "PB7(ADCB7/AC0-OUT/TDO)_12") (pintype "bidirectional"))
    )
    (net (code "92") (name "unconnected-(IC5-PD4(OC1A{slash}~{SS})-Pad29)") (class "Default")
      (node (ref "IC5") (pin "29") (pinfunction "PD4(OC1A/~{SS})_29") (pintype "bidirectional"))
    )
    (net (code "93") (name "unconnected-(IC5-PH6(CKE{slash}~{CS2}{slash}A18)-Pad61)") (class "Default")
      (node (ref "IC5") (pin "61") (pinfunction "PH6(CKE/~{CS2}/A18)_61") (pintype "bidirectional"))
    )
    (net (code "94") (name "unconnected-(IC5-PH7(CLK{slash}~{CS3}{slash}A19)-Pad62)") (class "Default")
      (node (ref "IC5") (pin "62") (pinfunction "PH7(CLK/~{CS3}/A19)_62") (pintype "bidirectional"))
    )
    (net (code "95") (name "unconnected-(IC5-PJ0(D0{slash}A0{slash}A8)-Pad65)") (class "Default")
      (node (ref "IC5") (pin "65") (pinfunction "PJ0(D0/A0/A8)_65") (pintype "bidirectional"))
    )
    (net (code "96") (name "unconnected-(IC5-PJ1(D1{slash}A1{slash}A9)-Pad66)") (class "Default")
      (node (ref "IC5") (pin "66") (pinfunction "PJ1(D1/A1/A9)_66") (pintype "bidirectional"))
    )
    (net (code "97") (name "unconnected-(IC5-PJ2(D2{slash}A2{slash}A10)-Pad67)") (class "Default")
      (node (ref "IC5") (pin "67") (pinfunction "PJ2(D2/A2/A10)_67") (pintype "bidirectional"))
    )
    (net (code "98") (name "unconnected-(IC5-PJ3(D3{slash}A3{slash}A11)-Pad68)") (class "Default")
      (node (ref "IC5") (pin "68") (pinfunction "PJ3(D3/A3/A11)_68") (pintype "bidirectional"))
    )
    (net (code "99") (name "unconnected-(IC5-PJ4(A8{slash}D4{slash}A4{slash}A12)-Pad69)") (class "Default")
      (node (ref "IC5") (pin "69") (pinfunction "PJ4(A8/D4/A4/A12)_69") (pintype "bidirectional"))
    )
    (net (code "100") (name "unconnected-(IC5-PJ5(A9{slash}D5{slash}A5{slash}A13)-Pad70)") (class "Default")
      (node (ref "IC5") (pin "70") (pinfunction "PJ5(A9/D5/A5/A13)_70") (pintype "bidirectional"))
    )
    (net (code "101") (name "unconnected-(IC5-PJ6(A10{slash}D6{slash}A6{slash}A14)-Pad71)") (class "Default")
      (node (ref "IC5") (pin "71") (pinfunction "PJ6(A10/D6/A6/A14)_71") (pintype "bidirectional"))
    )
    (net (code "102") (name "unconnected-(IC5-PJ7(A11{slash}D7{slash}A7{slash}A15)-Pad72)") (class "Default")
      (node (ref "IC5") (pin "72") (pinfunction "PJ7(A11/D7/A7/A15)_72") (pintype "bidirectional"))
    )
    (net (code "103") (name "unconnected-(IC5-PK1(A1{slash}A9{slash}A17)-Pad76)") (class "Default")
      (node (ref "IC5") (pin "76") (pinfunction "PK1(A1/A9/A17)_76") (pintype "bidirectional"))
    )
    (net (code "104") (name "unconnected-(IC5-PK2(A2{slash}A10{slash}A18)-Pad77)") (class "Default")
      (node (ref "IC5") (pin "77") (pinfunction "PK2(A2/A10/A18)_77") (pintype "bidirectional"))
    )
    (net (code "105") (name "unconnected-(IC5-PK3(A3{slash}A11{slash}A19)-Pad78)") (class "Default")
      (node (ref "IC5") (pin "78") (pinfunction "PK3(A3/A11/A19)_78") (pintype "bidirectional"))
    )
    (net (code "106") (name "unconnected-(IC5-PK4(A4{slash}A12{slash}A20)-Pad79)") (class "Default")
      (node (ref "IC5") (pin "79") (pinfunction "PK4(A4/A12/A20)_79") (pintype "bidirectional"))
    )
    (net (code "107") (name "unconnected-(IC5-PK5(A5{slash}A13{slash}A22)-Pad80)") (class "Default")
      (node (ref "IC5") (pin "80") (pinfunction "PK5(A5/A13/A22)_80") (pintype "bidirectional"))
    )
    (net (code "108") (name "unconnected-(IC5-PK6(A6{slash}A14{slash}A22)-Pad81)") (class "Default")
      (node (ref "IC5") (pin "81") (pinfunction "PK6(A6/A14/A22)_81") (pintype "bidirectional"))
    )
    (net (code "109") (name "unconnected-(IC5-PK7(A7{slash}A15{slash}A23)-Pad82)") (class "Default")
      (node (ref "IC5") (pin "82") (pinfunction "PK7(A7/A15/A23)_82") (pintype "bidirectional"))
    )
    (net (code "110") (name "unconnected-(JB1-Pad2)") (class "Default")
      (node (ref "JB1") (pin "2") (pinfunction "2_2") (pintype "passive"))
    )
    (net (code "111") (name "unconnected-(JB2-Pad2)") (class "Default")
      (node (ref "JB2") (pin "2") (pinfunction "2_2") (pintype "passive"))
    )
    (net (code "112") (name "unconnected-(JB2-Pad3)") (class "Default")
      (node (ref "JB2") (pin "3") (pinfunction "3_3") (pintype "passive"))
    )
    (net (code "113") (name "unconnected-(JB2-Pad4)") (class "Default")
      (node (ref "JB2") (pin "4") (pinfunction "4_4") (pintype "passive"))
    )
    (net (code "114") (name "unconnected-(JB2-Pad5)") (class "Default")
      (node (ref "JB2") (pin "5") (pinfunction "5_5") (pintype "passive"))
    )
    (net (code "115") (name "unconnected-(JB2-Pad7)") (class "Default")
      (node (ref "JB2") (pin "7") (pinfunction "7_7") (pintype "passive"))
    )
    (net (code "116") (name "unconnected-(JB2-Pad8)") (class "Default")
      (node (ref "JB2") (pin "8") (pinfunction "8_8") (pintype "passive"))
    )
    (net (code "117") (name "unconnected-(JB2-Pad9)") (class "Default")
      (node (ref "JB2") (pin "9") (pinfunction "9_9") (pintype "passive"))
    )
    (net (code "118") (name "unconnected-(JB2-Pad10)") (class "Default")
      (node (ref "JB2") (pin "10") (pinfunction "10_10") (pintype "passive"))
    )
    (net (code "119") (name "unconnected-(JC2-Pad3)") (class "Default")
      (node (ref "JC2") (pin "3") (pinfunction "3_3") (pintype "passive"))
    )
    (net (code "120") (name "unconnected-(JC2-Pad5)") (class "Default")
      (node (ref "JC2") (pin "5") (pinfunction "5_5") (pintype "passive"))
    )
    (net (code "121") (name "unconnected-(JC2-Pad7)") (class "Default")
      (node (ref "JC2") (pin "7") (pinfunction "7_7") (pintype "passive"))
    )
    (net (code "122") (name "unconnected-(JC2-Pad8)") (class "Default")
      (node (ref "JC2") (pin "8") (pinfunction "8_8") (pintype "passive"))
    )
    (net (code "123") (name "unconnected-(JC2-Pad9)") (class "Default")
      (node (ref "JC2") (pin "9") (pinfunction "9_9") (pintype "passive"))
    )
    (net (code "124") (name "unconnected-(JC2-Pad10)") (class "Default")
      (node (ref "JC2") (pin "10") (pinfunction "10_10") (pintype "passive"))
    )
    (net (code "125") (name "unconnected-(JC2-Pad11)") (class "Default")
      (node (ref "JC2") (pin "11") (pinfunction "11_11") (pintype "passive"))
    )
    (net (code "126") (name "unconnected-(JC2-Pad12)") (class "Default")
      (node (ref "JC2") (pin "12") (pinfunction "12_12") (pintype "passive"))
    )
    (net (code "127") (name "unconnected-(JC2-Pad13)") (class "Default")
      (node (ref "JC2") (pin "13") (pinfunction "13_13") (pintype "passive"))
    )
    (net (code "128") (name "unconnected-(JC2-Pad14)") (class "Default")
      (node (ref "JC2") (pin "14") (pinfunction "14_14") (pintype "passive"))
    )
    (net (code "129") (name "unconnected-(JC2-Pad15)") (class "Default")
      (node (ref "JC2") (pin "15") (pinfunction "15_15") (pintype "passive"))
    )
    (net (code "130") (name "unconnected-(JC2-Pad16)") (class "Default")
      (node (ref "JC2") (pin "16") (pinfunction "16_16") (pintype "passive"))
    )
    (net (code "131") (name "unconnected-(PDI_UC-NC-Pad3)") (class "Default")
      (node (ref "PDI_UC") (pin "3") (pinfunction "NC_3") (pintype "passive"))
    )
    (net (code "132") (name "unconnected-(PDI_UC-NC.-Pad4)") (class "Default")
      (node (ref "PDI_UC") (pin "4") (pinfunction "NC._4") (pintype "passive"))
    )
  )
)
